# Debouncer.net
KiCad netlist of a schematic drawn in EAGLE
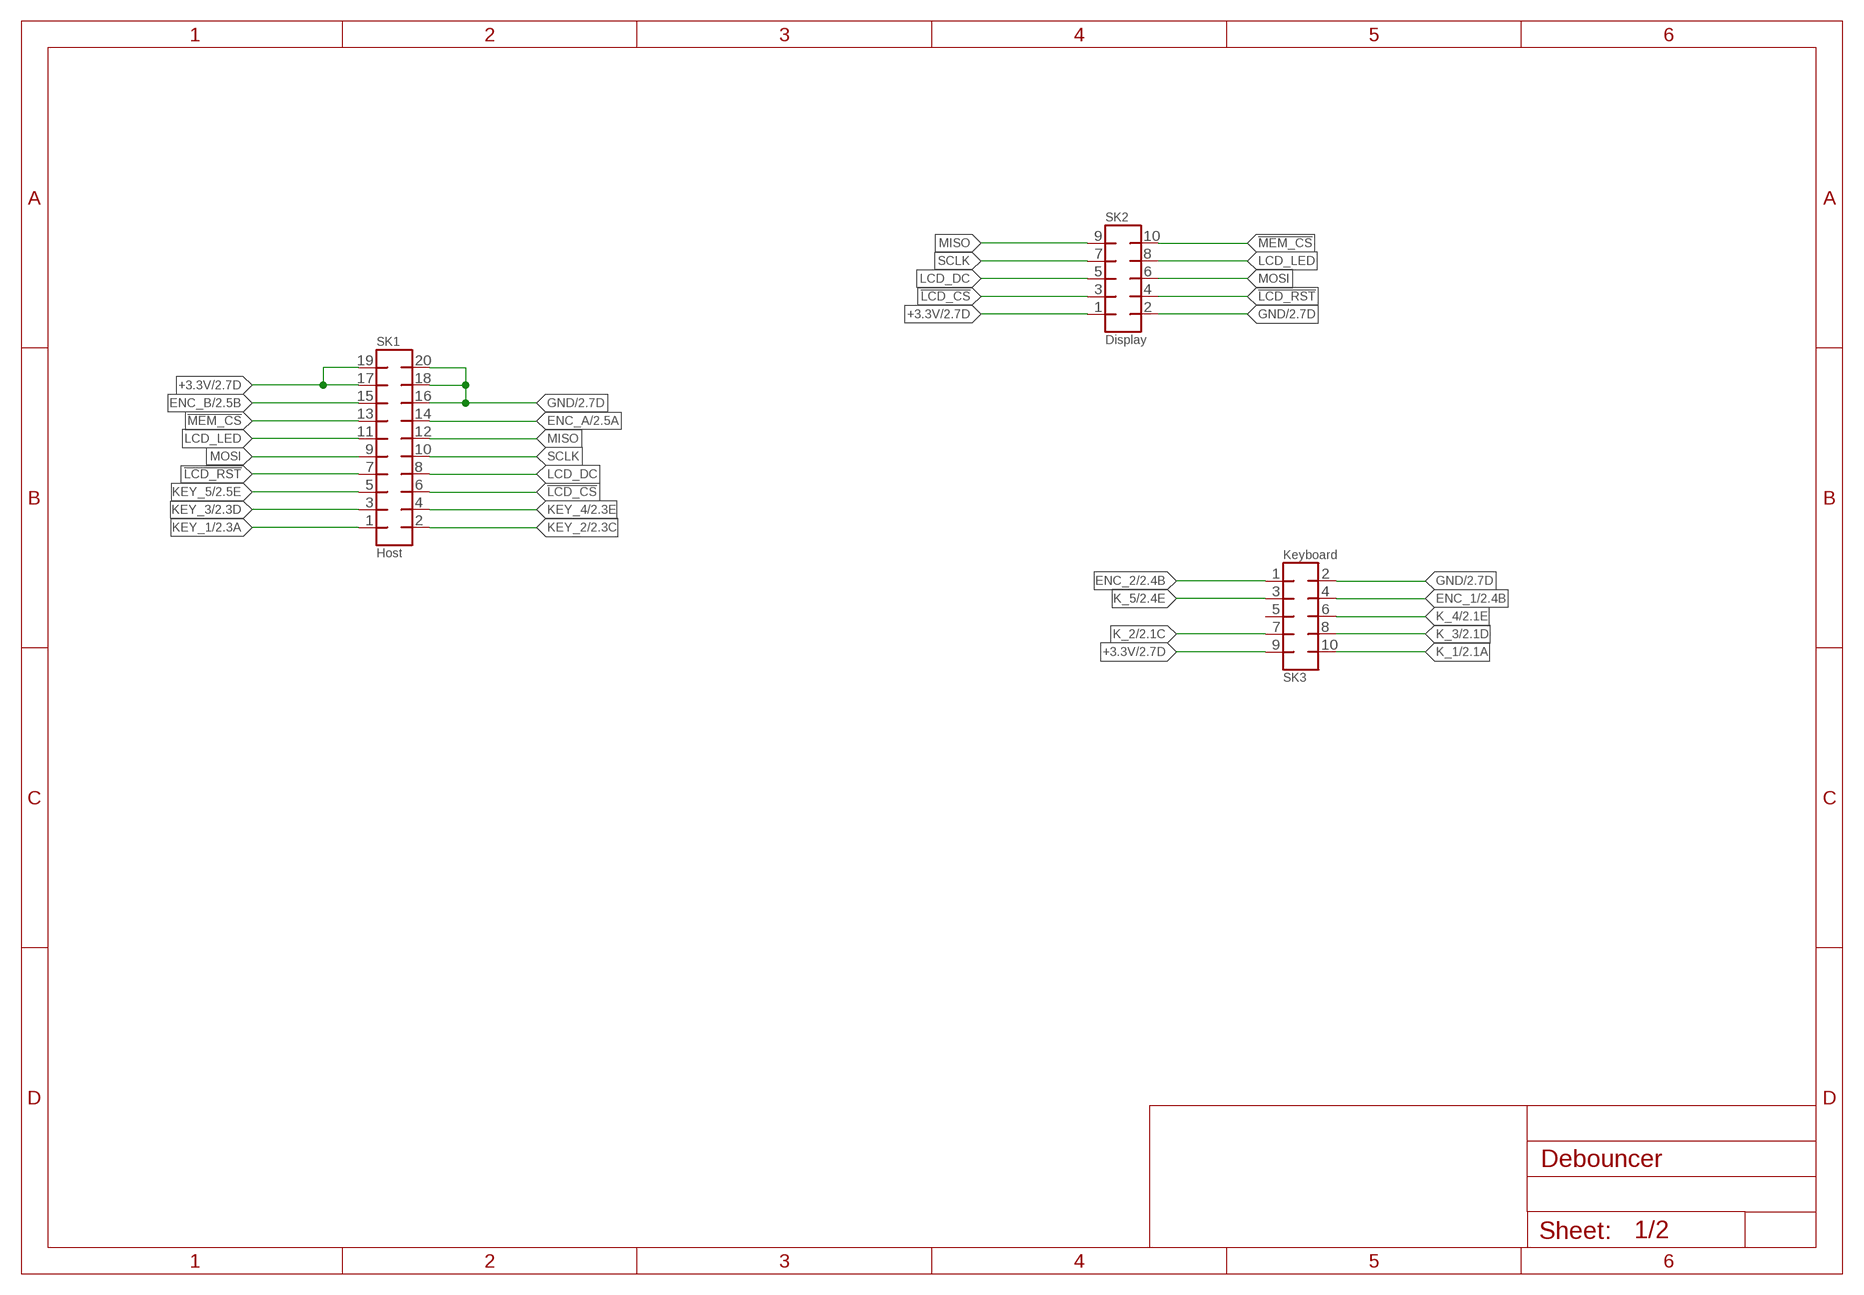
[diagram p0: schematic, sheet 1]
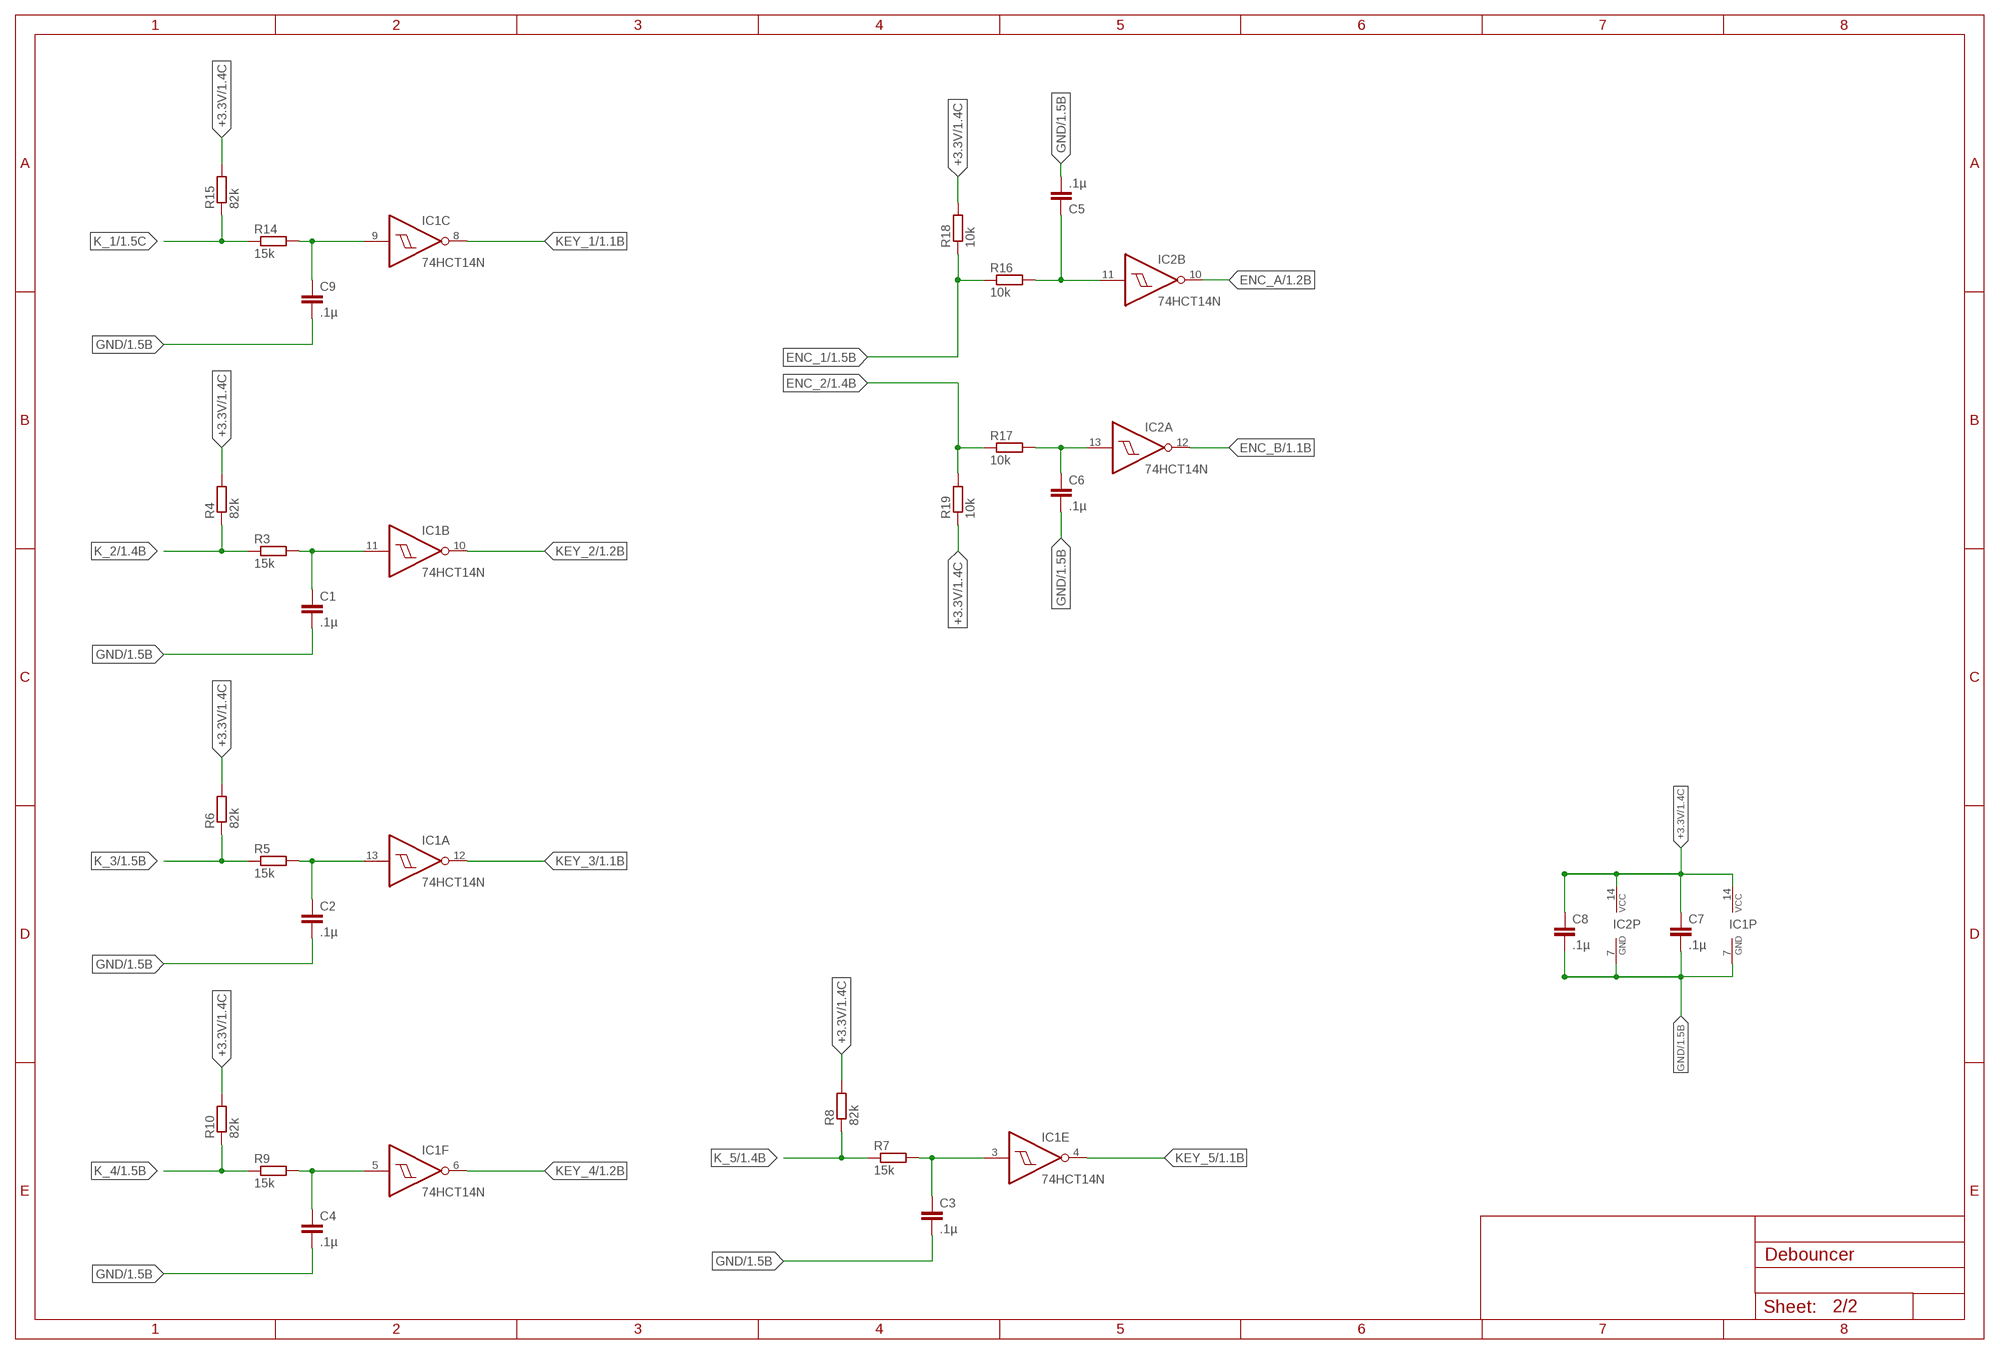
[diagram p1: schematic, sheet 2]

(export (version "E")
  (design (tool "Eeschema 10.0.6"))
  (components
    (comp (ref "C1")
      (value ".1µ")
      (footprint "eagle-import:C025-024X044")
      (libsource (lib "eagle-import") (part "C-EU025-024X044"))
    )
    (comp (ref "C2")
      (value ".1µ")
      (footprint "eagle-import:C025-024X044")
      (libsource (lib "eagle-import") (part "C-EU025-024X044"))
    )
    (comp (ref "C3")
      (value ".1µ")
      (footprint "eagle-import:C025-024X044")
      (libsource (lib "eagle-import") (part "C-EU025-024X044"))
    )
    (comp (ref "C4")
      (value ".1µ")
      (footprint "eagle-import:C025-024X044")
      (libsource (lib "eagle-import") (part "C-EU025-024X044"))
    )
    (comp (ref "C5")
      (value ".1µ")
      (footprint "eagle-import:C025-024X044")
      (libsource (lib "eagle-import") (part "C-EU025-024X044"))
    )
    (comp (ref "C6")
      (value ".1µ")
      (footprint "eagle-import:C025-024X044")
      (libsource (lib "eagle-import") (part "C-EU025-024X044"))
    )
    (comp (ref "C7")
      (value ".1µ")
      (footprint "eagle-import:C025-024X044")
      (libsource (lib "eagle-import") (part "C-EU025-024X044"))
    )
    (comp (ref "C8")
      (value ".1µ")
      (footprint "eagle-import:C025-024X044")
      (libsource (lib "eagle-import") (part "C-EU025-024X044"))
    )
    (comp (ref "C9")
      (value ".1µ")
      (footprint "eagle-import:C025-024X044")
      (libsource (lib "eagle-import") (part "C-EU025-024X044"))
    )
    (comp (ref "IC1")
      (value "74HCT14N")
      (footprint "eagle-import:DIL14")
      (libsource (lib "eagle-import") (part "7414NHCT"))
    )
    (comp (ref "IC2")
      (value "74HCT14N")
      (footprint "eagle-import:DIL14")
      (libsource (lib "eagle-import") (part "7414NHCT"))
    )
    (comp (ref "R3")
      (value "15k")
      (footprint "eagle-import:0204_7")
      (libsource (lib "eagle-import") (part "R-EU_0204/7"))
    )
    (comp (ref "R4")
      (value "82k")
      (footprint "eagle-import:0204_7")
      (libsource (lib "eagle-import") (part "R-EU_0204/7"))
    )
    (comp (ref "R5")
      (value "15k")
      (footprint "eagle-import:0204_7")
      (libsource (lib "eagle-import") (part "R-EU_0204/7"))
    )
    (comp (ref "R6")
      (value "82k")
      (footprint "eagle-import:0204_7")
      (libsource (lib "eagle-import") (part "R-EU_0204/7"))
    )
    (comp (ref "R7")
      (value "15k")
      (footprint "eagle-import:0204_7")
      (libsource (lib "eagle-import") (part "R-EU_0204/7"))
    )
    (comp (ref "R8")
      (value "82k")
      (footprint "eagle-import:0204_7")
      (libsource (lib "eagle-import") (part "R-EU_0204/7"))
    )
    (comp (ref "R9")
      (value "15k")
      (footprint "eagle-import:0204_7")
      (libsource (lib "eagle-import") (part "R-EU_0204/7"))
    )
    (comp (ref "R10")
      (value "82k")
      (footprint "eagle-import:0204_7")
      (libsource (lib "eagle-import") (part "R-EU_0204/7"))
    )
    (comp (ref "R14")
      (value "15k")
      (footprint "eagle-import:0204_7")
      (libsource (lib "eagle-import") (part "R-EU_0204/7"))
    )
    (comp (ref "R15")
      (value "82k")
      (footprint "eagle-import:0204_7")
      (libsource (lib "eagle-import") (part "R-EU_0204/7"))
    )
    (comp (ref "R16")
      (value "10k")
      (footprint "eagle-import:0204_7")
      (libsource (lib "eagle-import") (part "R-EU_0204/7"))
    )
    (comp (ref "R17")
      (value "10k")
      (footprint "eagle-import:0204_7")
      (libsource (lib "eagle-import") (part "R-EU_0204/7"))
    )
    (comp (ref "R18")
      (value "10k")
      (footprint "eagle-import:0204_7")
      (libsource (lib "eagle-import") (part "R-EU_0204/7"))
    )
    (comp (ref "R19")
      (value "10k")
      (footprint "eagle-import:0204_7")
      (libsource (lib "eagle-import") (part "R-EU_0204/7"))
    )
    (comp (ref "SK1")
      (value "Host")
      (footprint "eagle-import:AMP-215079-20")
      (libsource (lib "eagle-import") (part "MMATCH-20-PTH"))
    )
    (comp (ref "SK2")
      (value "Display")
      (footprint "eagle-import:AMP-215079-10")
      (libsource (lib "eagle-import") (part "MMATCH-10-PTH"))
    )
    (comp (ref "SK3")
      (value "Keyboard")
      (footprint "eagle-import:AMP-215079-10")
      (libsource (lib "eagle-import") (part "MMATCH-10-PTH"))
    )
  )
  (nets
    (net (code "1") (name "+3.3V") (class "Default")
      (node (ref "C7") (pin "1") (pinfunction "1_1") (pintype "passive"))
      (node (ref "C8") (pin "1") (pinfunction "1_1") (pintype "passive"))
      (node (ref "IC1") (pin "14") (pinfunction "VCC_14") (pintype "power_in"))
      (node (ref "IC2") (pin "14") (pinfunction "VCC_14") (pintype "power_in"))
      (node (ref "R10") (pin "2") (pinfunction "2_2") (pintype "passive"))
      (node (ref "R15") (pin "2") (pinfunction "2_2") (pintype "passive"))
      (node (ref "R18") (pin "2") (pinfunction "2_2") (pintype "passive"))
      (node (ref "R19") (pin "1") (pinfunction "1_1") (pintype "passive"))
      (node (ref "R4") (pin "2") (pinfunction "2_2") (pintype "passive"))
      (node (ref "R6") (pin "2") (pinfunction "2_2") (pintype "passive"))
      (node (ref "R8") (pin "2") (pinfunction "2_2") (pintype "passive"))
      (node (ref "SK1") (pin "17") (pinfunction "17_17") (pintype "bidirectional"))
      (node (ref "SK1") (pin "19") (pinfunction "19_19") (pintype "bidirectional"))
      (node (ref "SK2") (pin "1") (pinfunction "1_1") (pintype "bidirectional"))
      (node (ref "SK3") (pin "9") (pinfunction "9_9") (pintype "bidirectional"))
    )
    (net (code "2") (name "ENC_1") (class "Default")
      (node (ref "R16") (pin "1") (pinfunction "1_1") (pintype "passive"))
      (node (ref "R18") (pin "1") (pinfunction "1_1") (pintype "passive"))
      (node (ref "SK3") (pin "4") (pinfunction "4_4") (pintype "bidirectional"))
    )
    (net (code "3") (name "ENC_2") (class "Default")
      (node (ref "R17") (pin "1") (pinfunction "1_1") (pintype "passive"))
      (node (ref "R19") (pin "2") (pinfunction "2_2") (pintype "passive"))
      (node (ref "SK3") (pin "1") (pinfunction "1_1") (pintype "bidirectional"))
    )
    (net (code "4") (name "ENC_A") (class "Default")
      (node (ref "IC2") (pin "10") (pinfunction "O_10") (pintype "output"))
      (node (ref "SK1") (pin "14") (pinfunction "14_14") (pintype "bidirectional"))
    )
    (net (code "5") (name "ENC_B") (class "Default")
      (node (ref "IC2") (pin "12") (pinfunction "O_12") (pintype "output"))
      (node (ref "SK1") (pin "15") (pinfunction "15_15") (pintype "bidirectional"))
    )
    (net (code "6") (name "GND") (class "Default")
      (node (ref "C1") (pin "2") (pinfunction "2_2") (pintype "passive"))
      (node (ref "C2") (pin "2") (pinfunction "2_2") (pintype "passive"))
      (node (ref "C3") (pin "2") (pinfunction "2_2") (pintype "passive"))
      (node (ref "C4") (pin "2") (pinfunction "2_2") (pintype "passive"))
      (node (ref "C5") (pin "2") (pinfunction "2_2") (pintype "passive"))
      (node (ref "C6") (pin "2") (pinfunction "2_2") (pintype "passive"))
      (node (ref "C7") (pin "2") (pinfunction "2_2") (pintype "passive"))
      (node (ref "C8") (pin "2") (pinfunction "2_2") (pintype "passive"))
      (node (ref "C9") (pin "2") (pinfunction "2_2") (pintype "passive"))
      (node (ref "IC1") (pin "7") (pinfunction "GND_7") (pintype "power_in"))
      (node (ref "IC2") (pin "7") (pinfunction "GND_7") (pintype "power_in"))
      (node (ref "SK1") (pin "16") (pinfunction "16_16") (pintype "bidirectional"))
      (node (ref "SK1") (pin "18") (pinfunction "18_18") (pintype "bidirectional"))
      (node (ref "SK1") (pin "20") (pinfunction "20_20") (pintype "bidirectional"))
      (node (ref "SK2") (pin "2") (pinfunction "2_2") (pintype "bidirectional"))
      (node (ref "SK3") (pin "2") (pinfunction "2_2") (pintype "bidirectional"))
    )
    (net (code "7") (name "KEY_1") (class "Default")
      (node (ref "IC1") (pin "8") (pinfunction "O_8") (pintype "output"))
      (node (ref "SK1") (pin "1") (pinfunction "1_1") (pintype "bidirectional"))
    )
    (net (code "8") (name "KEY_2") (class "Default")
      (node (ref "IC1") (pin "10") (pinfunction "O_10") (pintype "output"))
      (node (ref "SK1") (pin "2") (pinfunction "2_2") (pintype "bidirectional"))
    )
    (net (code "9") (name "KEY_3") (class "Default")
      (node (ref "IC1") (pin "12") (pinfunction "O_12") (pintype "output"))
      (node (ref "SK1") (pin "3") (pinfunction "3_3") (pintype "bidirectional"))
    )
    (net (code "10") (name "KEY_4") (class "Default")
      (node (ref "IC1") (pin "6") (pinfunction "O_6") (pintype "output"))
      (node (ref "SK1") (pin "4") (pinfunction "4_4") (pintype "bidirectional"))
    )
    (net (code "11") (name "KEY_5") (class "Default")
      (node (ref "IC1") (pin "4") (pinfunction "O_4") (pintype "output"))
      (node (ref "SK1") (pin "5") (pinfunction "5_5") (pintype "bidirectional"))
    )
    (net (code "12") (name "K_1") (class "Default")
      (node (ref "R14") (pin "1") (pinfunction "1_1") (pintype "passive"))
      (node (ref "R15") (pin "1") (pinfunction "1_1") (pintype "passive"))
      (node (ref "SK3") (pin "10") (pinfunction "10_10") (pintype "bidirectional"))
    )
    (net (code "13") (name "K_2") (class "Default")
      (node (ref "R3") (pin "1") (pinfunction "1_1") (pintype "passive"))
      (node (ref "R4") (pin "1") (pinfunction "1_1") (pintype "passive"))
      (node (ref "SK3") (pin "7") (pinfunction "7_7") (pintype "bidirectional"))
    )
    (net (code "14") (name "K_3") (class "Default")
      (node (ref "R5") (pin "1") (pinfunction "1_1") (pintype "passive"))
      (node (ref "R6") (pin "1") (pinfunction "1_1") (pintype "passive"))
      (node (ref "SK3") (pin "8") (pinfunction "8_8") (pintype "bidirectional"))
    )
    (net (code "15") (name "K_4") (class "Default")
      (node (ref "R10") (pin "1") (pinfunction "1_1") (pintype "passive"))
      (node (ref "R9") (pin "1") (pinfunction "1_1") (pintype "passive"))
      (node (ref "SK3") (pin "6") (pinfunction "6_6") (pintype "bidirectional"))
    )
    (net (code "16") (name "K_5") (class "Default")
      (node (ref "R7") (pin "1") (pinfunction "1_1") (pintype "passive"))
      (node (ref "R8") (pin "1") (pinfunction "1_1") (pintype "passive"))
      (node (ref "SK3") (pin "3") (pinfunction "3_3") (pintype "bidirectional"))
    )
    (net (code "17") (name "LCD_DC") (class "Default")
      (node (ref "SK1") (pin "8") (pinfunction "8_8") (pintype "bidirectional"))
      (node (ref "SK2") (pin "5") (pinfunction "5_5") (pintype "bidirectional"))
    )
    (net (code "18") (name "LCD_LED") (class "Default")
      (node (ref "SK1") (pin "11") (pinfunction "11_11") (pintype "bidirectional"))
      (node (ref "SK2") (pin "8") (pinfunction "8_8") (pintype "bidirectional"))
    )
    (net (code "19") (name "MISO") (class "Default")
      (node (ref "SK1") (pin "12") (pinfunction "12_12") (pintype "bidirectional"))
      (node (ref "SK2") (pin "9") (pinfunction "9_9") (pintype "bidirectional"))
    )
    (net (code "20") (name "MOSI") (class "Default")
      (node (ref "SK1") (pin "9") (pinfunction "9_9") (pintype "bidirectional"))
      (node (ref "SK2") (pin "6") (pinfunction "6_6") (pintype "bidirectional"))
    )
    (net (code "21") (name "Net-(IC1A-I)") (class "Default")
      (node (ref "C2") (pin "1") (pinfunction "1_1") (pintype "passive"))
      (node (ref "IC1") (pin "13") (pinfunction "I_13") (pintype "input"))
      (node (ref "R5") (pin "2") (pinfunction "2_2") (pintype "passive"))
    )
    (net (code "22") (name "Net-(IC1B-I)") (class "Default")
      (node (ref "C1") (pin "1") (pinfunction "1_1") (pintype "passive"))
      (node (ref "IC1") (pin "11") (pinfunction "I_11") (pintype "input"))
      (node (ref "R3") (pin "2") (pinfunction "2_2") (pintype "passive"))
    )
    (net (code "23") (name "Net-(IC1C-I)") (class "Default")
      (node (ref "C9") (pin "1") (pinfunction "1_1") (pintype "passive"))
      (node (ref "IC1") (pin "9") (pinfunction "I_9") (pintype "input"))
      (node (ref "R14") (pin "2") (pinfunction "2_2") (pintype "passive"))
    )
    (net (code "24") (name "Net-(IC1E-I)") (class "Default")
      (node (ref "C3") (pin "1") (pinfunction "1_1") (pintype "passive"))
      (node (ref "IC1") (pin "3") (pinfunction "I_3") (pintype "input"))
      (node (ref "R7") (pin "2") (pinfunction "2_2") (pintype "passive"))
    )
    (net (code "25") (name "Net-(IC1F-I)") (class "Default")
      (node (ref "C4") (pin "1") (pinfunction "1_1") (pintype "passive"))
      (node (ref "IC1") (pin "5") (pinfunction "I_5") (pintype "input"))
      (node (ref "R9") (pin "2") (pinfunction "2_2") (pintype "passive"))
    )
    (net (code "26") (name "Net-(IC2A-I)") (class "Default")
      (node (ref "C6") (pin "1") (pinfunction "1_1") (pintype "passive"))
      (node (ref "IC2") (pin "13") (pinfunction "I_13") (pintype "input"))
      (node (ref "R17") (pin "2") (pinfunction "2_2") (pintype "passive"))
    )
    (net (code "27") (name "Net-(IC2B-I)") (class "Default")
      (node (ref "C5") (pin "1") (pinfunction "1_1") (pintype "passive"))
      (node (ref "IC2") (pin "11") (pinfunction "I_11") (pintype "input"))
      (node (ref "R16") (pin "2") (pinfunction "2_2") (pintype "passive"))
    )
    (net (code "28") (name "SCLK") (class "Default")
      (node (ref "SK1") (pin "10") (pinfunction "10_10") (pintype "bidirectional"))
      (node (ref "SK2") (pin "7") (pinfunction "7_7") (pintype "bidirectional"))
    )
    (net (code "29") (name "unconnected-(SK3-Pad5)") (class "Default")
      (node (ref "SK3") (pin "5") (pinfunction "5_5") (pintype "bidirectional"))
    )
    (net (code "30") (name "~{LCD_CS}") (class "Default")
      (node (ref "SK1") (pin "6") (pinfunction "6_6") (pintype "bidirectional"))
      (node (ref "SK2") (pin "3") (pinfunction "3_3") (pintype "bidirectional"))
    )
    (net (code "31") (name "~{LCD_RST}") (class "Default")
      (node (ref "SK1") (pin "7") (pinfunction "7_7") (pintype "bidirectional"))
      (node (ref "SK2") (pin "4") (pinfunction "4_4") (pintype "bidirectional"))
    )
    (net (code "32") (name "~{MEM_CS}") (class "Default")
      (node (ref "SK1") (pin "13") (pinfunction "13_13") (pintype "bidirectional"))
      (node (ref "SK2") (pin "10") (pinfunction "10_10") (pintype "bidirectional"))
    )
  )
)
